# Cerebro.net
KiCad netlist of a schematic drawn in EasyEDA Pro
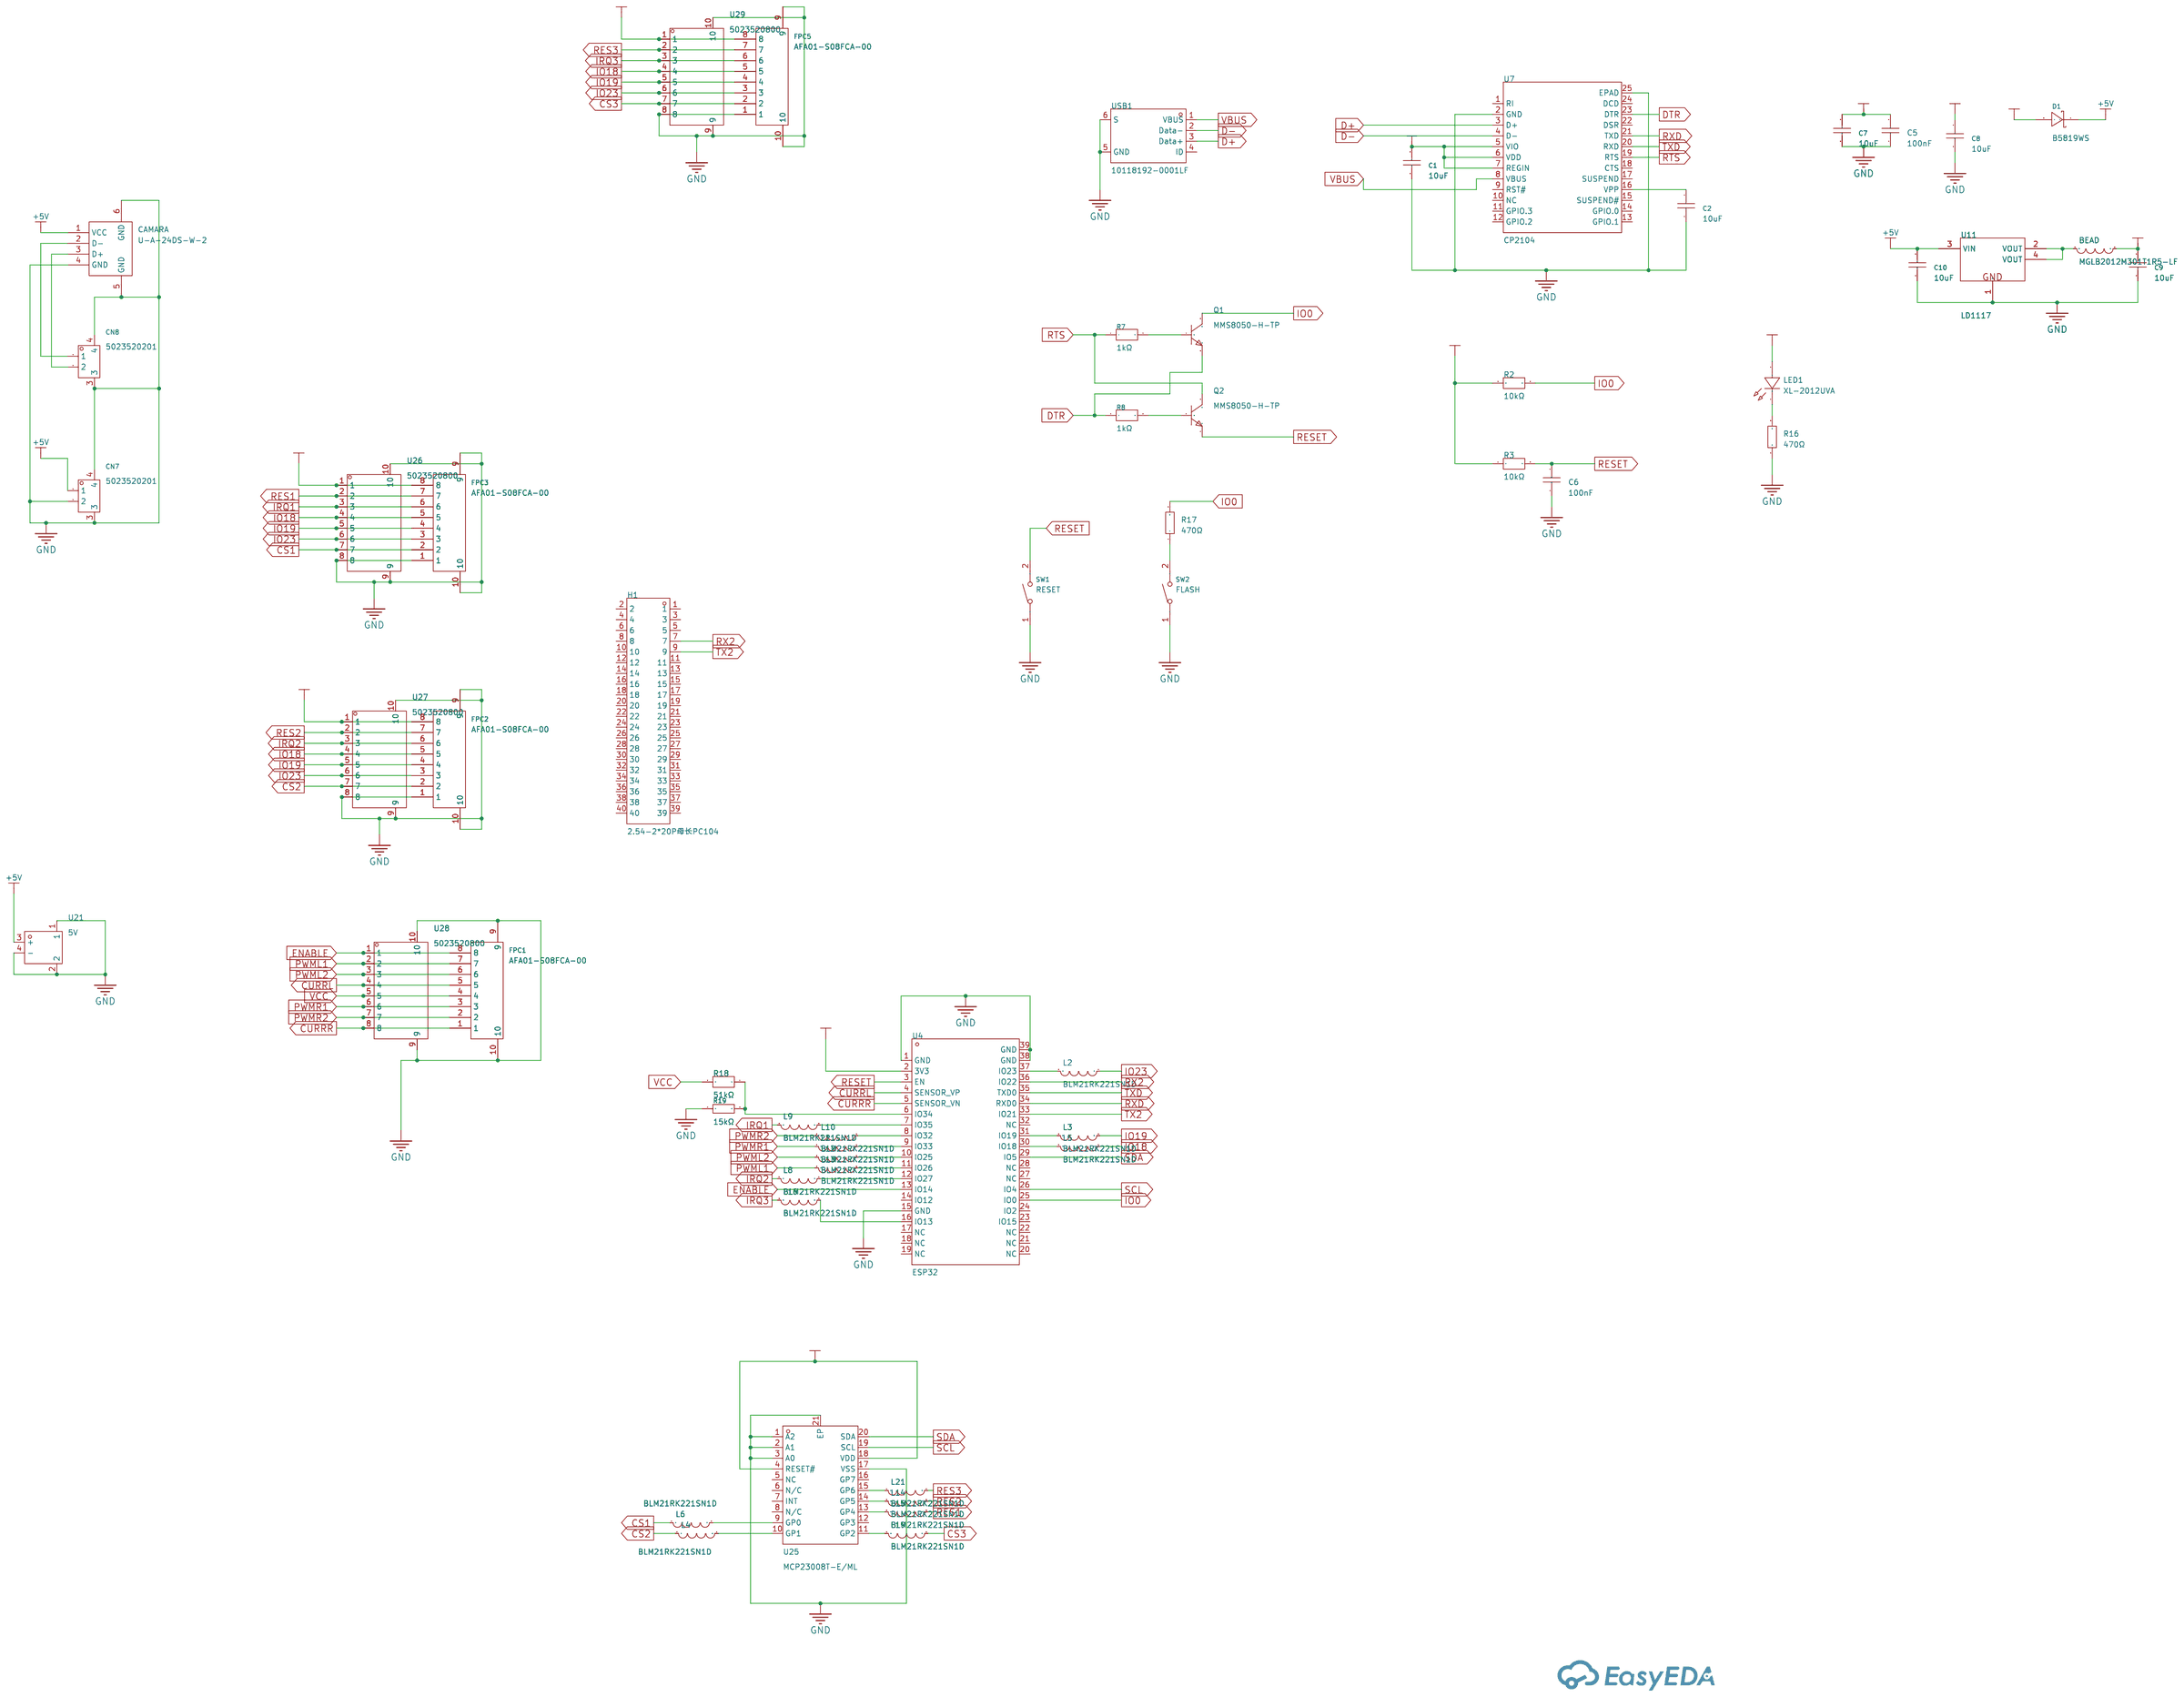
[diagram p0: schematic sheet]

(export (version "E")
  (design (tool "Eeschema 10.0.6"))
  (components
    (comp (ref "BEAD")
      (value "MGLB2012M301T1R5-LF")
      (footprint "easyedapro:L0805")
      (fields (field (name "Manufacturer") "microgate(麦捷科技)"))
      (libsource (lib "easyedapro") (part "MGLB2012M301T1R5-LF"))
    )
    (comp (ref "C1")
      (value "10uF")
      (footprint "easyedapro:C0805")
      (fields
        (field (name "Manufacturer Part") "CL21A106KPFNNNE")
        (field (name "Manufacturer") "SAMSUNG(三星)")
      )
      (libsource (lib "easyedapro") (part "CL21A106KPFNNNE"))
    )
    (comp (ref "C2")
      (value "10uF")
      (footprint "easyedapro:C0805")
      (fields
        (field (name "Manufacturer Part") "CL21A106KPFNNNE")
        (field (name "Manufacturer") "SAMSUNG(三星)")
      )
      (libsource (lib "easyedapro") (part "CL21A106KPFNNNE"))
    )
    (comp (ref "C5")
      (value "100nF")
      (footprint "easyedapro:C0805")
      (description "Capacitance:100nF Tolerance:±5% Tolerance:±5% Voltage Rating:50V Temperature Coefficient:X7R")
      (fields (field (name "Manufacturer Part") "0805B104J500NT") (field (name "Manufacturer") "FH(风华)"))
      (libsource (lib "easyedapro") (part "0805B104J500NT"))
    )
    (comp (ref "C6")
      (value "100nF")
      (footprint "easyedapro:C0805")
      (description "Capacitance:100nF Tolerance:±5% Tolerance:±5% Voltage Rating:50V Temperature Coefficient:X7R")
      (fields (field (name "Manufacturer Part") "0805B104J500NT") (field (name "Manufacturer") "FH(风华)"))
      (libsource (lib "easyedapro") (part "0805B104J500NT"))
    )
    (comp (ref "C7")
      (value "10uF")
      (footprint "easyedapro:C0805")
      (fields
        (field (name "Manufacturer Part") "CL21A106KPFNNNE")
        (field (name "Manufacturer") "SAMSUNG(三星)")
      )
      (libsource (lib "easyedapro") (part "CL21A106KPFNNNE"))
    )
    (comp (ref "C8")
      (value "10uF")
      (footprint "easyedapro:C0805")
      (fields
        (field (name "Manufacturer Part") "CL21A106KPFNNNE")
        (field (name "Manufacturer") "SAMSUNG(三星)")
      )
      (libsource (lib "easyedapro") (part "CL21A106KPFNNNE"))
    )
    (comp (ref "C9")
      (value "10uF")
      (footprint "easyedapro:C0805")
      (fields
        (field (name "Manufacturer Part") "CL21A106KPFNNNE")
        (field (name "Manufacturer") "SAMSUNG(三星)")
      )
      (libsource (lib "easyedapro") (part "CL21A106KPFNNNE"))
    )
    (comp (ref "C10")
      (value "10uF")
      (footprint "easyedapro:C0805")
      (fields
        (field (name "Manufacturer Part") "CL21A106KPFNNNE")
        (field (name "Manufacturer") "SAMSUNG(三星)")
      )
      (libsource (lib "easyedapro") (part "CL21A106KPFNNNE"))
    )
    (comp (ref "CAMARA")
      (value "U-A-24DS-W-2")
      (footprint "easyedapro:USB-A-SMD_U-A-24DS-Y-1")
      (fields (field (name "Manufacturer") "韩国韩荣"))
      (libsource (lib "easyedapro") (part "U-A-24DS-W-2"))
    )
    (comp (ref "CN7")
      (value "5023520201")
      (footprint "easyedapro:CONN-SMD_2P-P2.00_MOLEX_5023520201")
      (fields (field (name "Manufacturer") "MOLEX"))
      (libsource (lib "easyedapro") (part "5023520201"))
    )
    (comp (ref "CN8")
      (value "5023520201")
      (footprint "easyedapro:CONN-SMD_2P-P2.00_MOLEX_5023520201")
      (fields (field (name "Manufacturer") "MOLEX"))
      (libsource (lib "easyedapro") (part "5023520201"))
    )
    (comp (ref "D1")
      (value "B5819WS")
      (footprint "easyedapro:SOD-323_L1.8-W1.3-LS2.5-RD")
      (fields (field (name "Manufacturer Part") "B5819WS-TP") (field (name "Manufacturer") "MCC(美微科)"))
      (libsource (lib "easyedapro") (part "B5819WS-TP"))
    )
    (comp (ref "FPC1")
      (value "AFA01-S08FCA-00")
      (footprint "easyedapro:FPC-SMD_8P-P1.00_FGS-XJ-H2.0")
      (fields (field (name "Manufacturer") "JS(钜硕电子)"))
      (libsource (lib "easyedapro") (part "AFA01-S08FCA-00"))
    )
    (comp (ref "FPC2")
      (value "AFA01-S08FCA-00")
      (footprint "easyedapro:FPC-SMD_8P-P1.00_FGS-XJ-H2.0")
      (fields (field (name "Manufacturer") "JS(钜硕电子)"))
      (libsource (lib "easyedapro") (part "AFA01-S08FCA-00"))
    )
    (comp (ref "FPC3")
      (value "AFA01-S08FCA-00")
      (footprint "easyedapro:FPC-SMD_8P-P1.00_FGS-XJ-H2.0")
      (fields (field (name "Manufacturer") "JS(钜硕电子)"))
      (libsource (lib "easyedapro") (part "AFA01-S08FCA-00"))
    )
    (comp (ref "FPC5")
      (value "AFA01-S08FCA-00")
      (footprint "easyedapro:FPC-SMD_8P-P1.00_FGS-XJ-H2.0")
      (fields (field (name "Manufacturer") "JS(钜硕电子)"))
      (libsource (lib "easyedapro") (part "AFA01-S08FCA-00"))
    )
    (comp (ref "H1")
      (value "2.54-2*20P母长PC104")
      (footprint "easyedapro:HDR-TH_40P-P2.54-V-F-R2-C20-S2.54-2")
      (fields (field (name "Manufacturer") "BOOMELE(博穆精密)"))
      (libsource (lib "easyedapro") (part "2.54mm 2*20P"))
    )
    (comp (ref "L2")
      (value "BLM21RK221SN1D")
      (footprint "easyedapro:L0805")
      (fields (field (name "Manufacturer") "muRata(村田)"))
      (libsource (lib "easyedapro") (part "BLM21RK221SN1D"))
    )
    (comp (ref "L3")
      (value "BLM21RK221SN1D")
      (footprint "easyedapro:L0805")
      (fields (field (name "Manufacturer") "muRata(村田)"))
      (libsource (lib "easyedapro") (part "BLM21RK221SN1D"))
    )
    (comp (ref "L4")
      (value "BLM21RK221SN1D")
      (footprint "easyedapro:L0805")
      (fields (field (name "Manufacturer") "muRata(村田)"))
      (libsource (lib "easyedapro") (part "BLM21RK221SN1D"))
    )
    (comp (ref "L5")
      (value "BLM21RK221SN1D")
      (footprint "easyedapro:L0805")
      (fields (field (name "Manufacturer") "muRata(村田)"))
      (libsource (lib "easyedapro") (part "BLM21RK221SN1D"))
    )
    (comp (ref "L6")
      (value "BLM21RK221SN1D")
      (footprint "easyedapro:L0805")
      (fields (field (name "Manufacturer") "muRata(村田)"))
      (libsource (lib "easyedapro") (part "BLM21RK221SN1D"))
    )
    (comp (ref "L8")
      (value "BLM21RK221SN1D")
      (footprint "easyedapro:L0805")
      (fields (field (name "Manufacturer") "muRata(村田)"))
      (libsource (lib "easyedapro") (part "BLM21RK221SN1D"))
    )
    (comp (ref "L9")
      (value "BLM21RK221SN1D")
      (footprint "easyedapro:L0805")
      (fields (field (name "Manufacturer") "muRata(村田)"))
      (libsource (lib "easyedapro") (part "BLM21RK221SN1D"))
    )
    (comp (ref "L10")
      (value "BLM21RK221SN1D")
      (footprint "easyedapro:L0805")
      (fields (field (name "Manufacturer") "muRata(村田)"))
      (libsource (lib "easyedapro") (part "BLM21RK221SN1D"))
    )
    (comp (ref "L11")
      (value "BLM21RK221SN1D")
      (footprint "easyedapro:L0805")
      (fields (field (name "Manufacturer") "muRata(村田)"))
      (libsource (lib "easyedapro") (part "BLM21RK221SN1D"))
    )
    (comp (ref "L12")
      (value "BLM21RK221SN1D")
      (footprint "easyedapro:L0805")
      (fields (field (name "Manufacturer") "muRata(村田)"))
      (libsource (lib "easyedapro") (part "BLM21RK221SN1D"))
    )
    (comp (ref "L13")
      (value "BLM21RK221SN1D")
      (footprint "easyedapro:L0805")
      (fields (field (name "Manufacturer") "muRata(村田)"))
      (libsource (lib "easyedapro") (part "BLM21RK221SN1D"))
    )
    (comp (ref "L14")
      (value "BLM21RK221SN1D")
      (footprint "easyedapro:L0805")
      (fields (field (name "Manufacturer") "muRata(村田)"))
      (libsource (lib "easyedapro") (part "BLM21RK221SN1D"))
    )
    (comp (ref "L15")
      (value "BLM21RK221SN1D")
      (footprint "easyedapro:L0805")
      (fields (field (name "Manufacturer") "muRata(村田)"))
      (libsource (lib "easyedapro") (part "BLM21RK221SN1D"))
    )
    (comp (ref "L16")
      (value "BLM21RK221SN1D")
      (footprint "easyedapro:L0805")
      (fields (field (name "Manufacturer") "muRata(村田)"))
      (libsource (lib "easyedapro") (part "BLM21RK221SN1D"))
    )
    (comp (ref "L19")
      (value "BLM21RK221SN1D")
      (footprint "easyedapro:L0805")
      (fields (field (name "Manufacturer") "muRata(村田)"))
      (libsource (lib "easyedapro") (part "BLM21RK221SN1D"))
    )
    (comp (ref "L21")
      (value "BLM21RK221SN1D")
      (footprint "easyedapro:L0805")
      (fields (field (name "Manufacturer") "muRata(村田)"))
      (libsource (lib "easyedapro") (part "BLM21RK221SN1D"))
    )
    (comp (ref "LED1")
      (value "XL-2012UVA")
      (footprint "easyedapro:LED0805-RD")
      (fields (field (name "Manufacturer") "XINGLIGHT(成兴光)"))
      (libsource (lib "easyedapro") (part "XL-2012UVA"))
    )
    (comp (ref "Q1")
      (value "MMS8050-H-TP")
      (footprint "easyedapro:SOT-23-3_L2.9-W1.3-P1.90-LS2.4-BR")
      (fields (field (name "Manufacturer") "MCC(美微科)"))
      (libsource (lib "easyedapro") (part "MMS8050-H-TP"))
    )
    (comp (ref "Q2")
      (value "MMS8050-H-TP")
      (footprint "easyedapro:SOT-23-3_L2.9-W1.3-P1.90-LS2.4-BR")
      (fields (field (name "Manufacturer") "MCC(美微科)"))
      (libsource (lib "easyedapro") (part "MMS8050-H-TP"))
    )
    (comp (ref "R2")
      (value "10kΩ")
      (footprint "easyedapro:R0805")
      (fields (field (name "Manufacturer Part") "ERJP06F1002V") (field (name "Manufacturer") "PANASONIC(松下)"))
      (libsource (lib "easyedapro") (part "ERJP06F1002V"))
    )
    (comp (ref "R3")
      (value "10kΩ")
      (footprint "easyedapro:R0805")
      (fields (field (name "Manufacturer Part") "ERJP06F1002V") (field (name "Manufacturer") "PANASONIC(松下)"))
      (libsource (lib "easyedapro") (part "ERJP06F1002V"))
    )
    (comp (ref "R7")
      (value "1kΩ")
      (footprint "easyedapro:R0805")
      (fields (field (name "Manufacturer Part") "ERJP06F1001V") (field (name "Manufacturer") "PANASONIC(松下)"))
      (libsource (lib "easyedapro") (part "ERJP06F1001V"))
    )
    (comp (ref "R8")
      (value "1kΩ")
      (footprint "easyedapro:R0805")
      (fields (field (name "Manufacturer Part") "ERJP06F1001V") (field (name "Manufacturer") "PANASONIC(松下)"))
      (libsource (lib "easyedapro") (part "ERJP06F1001V"))
    )
    (comp (ref "R16")
      (value "470Ω")
      (footprint "easyedapro:R0805")
      (fields (field (name "Manufacturer Part") "RC0805FR-07470RL") (field (name "Manufacturer") "YAGEO(国巨)"))
      (libsource (lib "easyedapro") (part "RC0805FR-07470RL"))
    )
    (comp (ref "R17")
      (value "470Ω")
      (footprint "easyedapro:R0805")
      (fields (field (name "Manufacturer Part") "RC0805FR-07470RL") (field (name "Manufacturer") "YAGEO(国巨)"))
      (libsource (lib "easyedapro") (part "RC0805FR-07470RL"))
    )
    (comp (ref "R18")
      (value "51kΩ")
      (footprint "easyedapro:R0805")
      (fields (field (name "Manufacturer Part") "FRC0805F5102TS") (field (name "Manufacturer") "FOJAN(富捷)"))
      (libsource (lib "easyedapro") (part "FRC0805F5102TS"))
    )
    (comp (ref "R19")
      (value "15kΩ")
      (footprint "easyedapro:R0805")
      (fields
        (field (name "Manufacturer Part") "0805W8F1502T5E")
        (field (name "Manufacturer") "UNI-ROYAL(厚声)")
      )
      (libsource (lib "easyedapro") (part "0805W8F1502T5E"))
    )
    (comp (ref "SW1")
      (value "RESET")
      (footprint "easyedapro:SW-SMD_L3.9-W3.0-P4.45")
      (fields (field (name "Manufacturer Part") "TS-1088-AR02016") (field (name "Manufacturer") "XUNPU(讯普)"))
      (libsource (lib "easyedapro") (part "TS-1088-AR02016"))
    )
    (comp (ref "SW2")
      (value "FLASH")
      (footprint "easyedapro:SW-SMD_L3.9-W3.0-P4.45")
      (fields (field (name "Manufacturer Part") "TS-1088-AR02016") (field (name "Manufacturer") "XUNPU(讯普)"))
      (libsource (lib "easyedapro") (part "TS-1088-AR02016"))
    )
    (comp (ref "U4")
      (value "ESP32")
      (footprint "easyedapro:WIFI-SMD_ESP32-WROVER-IE8MB")
      (fields
        (field (name "Manufacturer Part") "ESP32-WROVER-E-N8R8")
        (field (name "Manufacturer") "ESPRESSIF(乐鑫)")
      )
      (libsource (lib "easyedapro") (part "ESP32-WROVER-E-N8R8"))
    )
    (comp (ref "U7")
      (value "CP2104")
      (footprint "easyedapro:QFN-24_L4.0-W4.0-P0.50-BL-EP2.7")
      (fields
        (field (name "Manufacturer Part") "CP2104-F03-GMR")
        (field (name "Manufacturer") "SKYWORKS/SILICON LABS(芯科)")
      )
      (libsource (lib "easyedapro") (part "CP2104-F03-GM"))
    )
    (comp (ref "U11")
      (value "LD1117")
      (footprint "easyedapro:SOT-223-4_L6.5-W3.5-P2.30-LS7.0-BR")
      (fields (field (name "Manufacturer Part") "LD1117S33CTR") (field (name "Manufacturer") "ST(意法半导体)"))
      (libsource (lib "easyedapro") (part "LD1117S33CTR"))
    )
    (comp (ref "U21")
      (value "5V")
      (footprint "easyedapro:TH_2P-XT60PW-F")
      (fields (field (name "Manufacturer Part") "XT60PW-F") (field (name "Manufacturer") "AMASS(艾迈斯)"))
      (libsource (lib "easyedapro") (part "XT60PW-F_C428722"))
    )
    (comp (ref "U25")
      (value "MCP23008T-E/ML")
      (footprint "easyedapro:UQFN-20_L4.0-W4.0-P0.50-BL-EP2.7")
      (fields (field (name "Manufacturer") "MICROCHIP(美国微芯)"))
      (libsource (lib "easyedapro") (part "MCP23008T-E/ML"))
    )
    (comp (ref "U26")
      (value "5023520800")
      (footprint "easyedapro:CONN-SMD_5023520800")
      (fields (field (name "Manufacturer") "MOLEX"))
      (libsource (lib "easyedapro") (part "5023520800"))
    )
    (comp (ref "U27")
      (value "5023520800")
      (footprint "easyedapro:CONN-SMD_5023520800")
      (fields (field (name "Manufacturer") "MOLEX"))
      (libsource (lib "easyedapro") (part "5023520800"))
    )
    (comp (ref "U28")
      (value "5023520800")
      (footprint "easyedapro:CONN-SMD_5023520800")
      (fields (field (name "Manufacturer") "MOLEX"))
      (libsource (lib "easyedapro") (part "5023520800"))
    )
    (comp (ref "U29")
      (value "5023520800")
      (footprint "easyedapro:CONN-SMD_5023520800")
      (fields (field (name "Manufacturer") "MOLEX"))
      (libsource (lib "easyedapro") (part "5023520800"))
    )
    (comp (ref "USB1")
      (value "10118192-0001LF")
      (footprint "easyedapro:MICRO-USB-SMD_10118192-0001LF_1")
      (fields (field (name "Manufacturer") "Amphenol"))
      (libsource (lib "easyedapro") (part "10118192-0001LF"))
    )
  )
  (nets
    (net (code "1") (name "+3V3") (class "Default")
      (node (ref "BEAD") (pin "1") (pinfunction "1_1") (pintype "unspecified"))
      (node (ref "C1") (pin "2") (pinfunction "2_2") (pintype "input"))
      (node (ref "C8") (pin "2") (pinfunction "2_2") (pintype "input"))
      (node (ref "C9") (pin "2") (pinfunction "2_2") (pintype "input"))
      (node (ref "FPC2") (pin "8") (pinfunction "8_8") (pintype "input"))
      (node (ref "FPC3") (pin "8") (pinfunction "8_8") (pintype "input"))
      (node (ref "FPC5") (pin "8") (pinfunction "8_8") (pintype "input"))
      (node (ref "LED1") (pin "2") (pinfunction "A_2") (pintype "unspecified"))
      (node (ref "R2") (pin "1") (pinfunction "1_1") (pintype "unspecified"))
      (node (ref "R3") (pin "1") (pinfunction "1_1") (pintype "unspecified"))
      (node (ref "U25") (pin "18") (pinfunction "VDD_18") (pintype "unspecified"))
      (node (ref "U25") (pin "4") (pinfunction "RESET#_4") (pintype "unspecified"))
      (node (ref "U26") (pin "1") (pinfunction "1_1") (pintype "unspecified"))
      (node (ref "U27") (pin "1") (pinfunction "1_1") (pintype "unspecified"))
      (node (ref "U29") (pin "1") (pinfunction "1_1") (pintype "unspecified"))
      (node (ref "U4") (pin "2") (pinfunction "3V3_2") (pintype "unspecified"))
      (node (ref "U7") (pin "5") (pinfunction "VIO_5") (pintype "unspecified"))
      (node (ref "U7") (pin "6") (pinfunction "VDD_6") (pintype "unspecified"))
      (node (ref "U7") (pin "7") (pinfunction "REGIN_7") (pintype "unspecified"))
    )
    (net (code "2") (name "+5V") (class "Default")
      (node (ref "C10") (pin "2") (pinfunction "2_2") (pintype "input"))
      (node (ref "CAMARA") (pin "1") (pinfunction "VCC_1") (pintype "unspecified"))
      (node (ref "CN7") (pin "1") (pinfunction "1_1") (pintype "input"))
      (node (ref "D1") (pin "1") (pinfunction "K_1") (pintype "input"))
      (node (ref "U11") (pin "3") (pinfunction "VIN_3") (pintype "unspecified"))
      (node (ref "U21") (pin "3") (pinfunction "+_3") (pintype "unspecified"))
    )
    (net (code "3") (name "CS1") (class "Default")
      (node (ref "FPC3") (pin "2") (pinfunction "2_2") (pintype "input"))
      (node (ref "L6") (pin "1") (pinfunction "1_1") (pintype "unspecified"))
      (node (ref "U26") (pin "7") (pinfunction "7_7") (pintype "unspecified"))
    )
    (net (code "4") (name "CS2") (class "Default")
      (node (ref "FPC2") (pin "2") (pinfunction "2_2") (pintype "input"))
      (node (ref "L4") (pin "1") (pinfunction "1_1") (pintype "unspecified"))
      (node (ref "U27") (pin "7") (pinfunction "7_7") (pintype "unspecified"))
    )
    (net (code "5") (name "CS3") (class "Default")
      (node (ref "FPC5") (pin "2") (pinfunction "2_2") (pintype "input"))
      (node (ref "L19") (pin "1") (pinfunction "1_1") (pintype "unspecified"))
      (node (ref "U29") (pin "7") (pinfunction "7_7") (pintype "unspecified"))
    )
    (net (code "6") (name "CURRL") (class "Default")
      (node (ref "FPC1") (pin "5") (pinfunction "5_5") (pintype "input"))
      (node (ref "U28") (pin "4") (pinfunction "4_4") (pintype "unspecified"))
      (node (ref "U4") (pin "4") (pinfunction "SENSOR_VP_4") (pintype "unspecified"))
    )
    (net (code "7") (name "CURRR") (class "Default")
      (node (ref "FPC1") (pin "1") (pinfunction "1_1") (pintype "input"))
      (node (ref "U28") (pin "8") (pinfunction "8_8") (pintype "unspecified"))
      (node (ref "U4") (pin "5") (pinfunction "SENSOR_VN_5") (pintype "unspecified"))
    )
    (net (code "8") (name "D+") (class "Default")
      (node (ref "U7") (pin "3") (pinfunction "D+_3") (pintype "unspecified"))
      (node (ref "USB1") (pin "3") (pinfunction "Data+_3") (pintype "unspecified"))
    )
    (net (code "9") (name "D-") (class "Default")
      (node (ref "U7") (pin "4") (pinfunction "D-_4") (pintype "unspecified"))
      (node (ref "USB1") (pin "2") (pinfunction "Data-_2") (pintype "unspecified"))
    )
    (net (code "10") (name "DTR") (class "Default")
      (node (ref "Q1") (pin "2") (pinfunction "E_2") (pintype "input"))
      (node (ref "R8") (pin "1") (pinfunction "1_1") (pintype "input"))
      (node (ref "U7") (pin "23") (pinfunction "DTR_23") (pintype "unspecified"))
    )
    (net (code "11") (name "ENABLE") (class "Default")
      (node (ref "FPC1") (pin "8") (pinfunction "8_8") (pintype "input"))
      (node (ref "U28") (pin "1") (pinfunction "1_1") (pintype "unspecified"))
      (node (ref "U4") (pin "13") (pinfunction "IO14_13") (pintype "unspecified"))
    )
    (net (code "12") (name "GND") (class "Default")
      (node (ref "C1") (pin "1") (pinfunction "1_1") (pintype "input"))
      (node (ref "C10") (pin "1") (pinfunction "1_1") (pintype "input"))
      (node (ref "C2") (pin "1") (pinfunction "1_1") (pintype "input"))
      (node (ref "C5") (pin "1") (pinfunction "1_1") (pintype "input"))
      (node (ref "C6") (pin "1") (pinfunction "1_1") (pintype "input"))
      (node (ref "C7") (pin "1") (pinfunction "1_1") (pintype "input"))
      (node (ref "C8") (pin "1") (pinfunction "1_1") (pintype "input"))
      (node (ref "C9") (pin "1") (pinfunction "1_1") (pintype "input"))
      (node (ref "CAMARA") (pin "4") (pinfunction "GND_4") (pintype "unspecified"))
      (node (ref "CAMARA") (pin "5") (pinfunction "GND_5") (pintype "unspecified"))
      (node (ref "CAMARA") (pin "6") (pinfunction "GND_6") (pintype "unspecified"))
      (node (ref "CN7") (pin "2") (pinfunction "2_2") (pintype "input"))
      (node (ref "CN7") (pin "3") (pinfunction "3_3") (pintype "input"))
      (node (ref "CN7") (pin "4") (pinfunction "4_4") (pintype "input"))
      (node (ref "CN8") (pin "3") (pinfunction "3_3") (pintype "input"))
      (node (ref "CN8") (pin "4") (pinfunction "4_4") (pintype "input"))
      (node (ref "FPC1") (pin "10") (pinfunction "10_10") (pintype "input"))
      (node (ref "FPC1") (pin "9") (pinfunction "9_9") (pintype "input"))
      (node (ref "FPC2") (pin "1") (pinfunction "1_1") (pintype "input"))
      (node (ref "FPC2") (pin "10") (pinfunction "10_10") (pintype "input"))
      (node (ref "FPC2") (pin "9") (pinfunction "9_9") (pintype "input"))
      (node (ref "FPC3") (pin "1") (pinfunction "1_1") (pintype "input"))
      (node (ref "FPC3") (pin "10") (pinfunction "10_10") (pintype "input"))
      (node (ref "FPC3") (pin "9") (pinfunction "9_9") (pintype "input"))
      (node (ref "FPC5") (pin "1") (pinfunction "1_1") (pintype "input"))
      (node (ref "FPC5") (pin "10") (pinfunction "10_10") (pintype "input"))
      (node (ref "FPC5") (pin "9") (pinfunction "9_9") (pintype "input"))
      (node (ref "R16") (pin "1") (pinfunction "1_1") (pintype "input"))
      (node (ref "R19") (pin "1") (pinfunction "1_1") (pintype "input"))
      (node (ref "SW1") (pin "1") (pinfunction "1_1") (pintype "input"))
      (node (ref "SW2") (pin "1") (pinfunction "1_1") (pintype "input"))
      (node (ref "U11") (pin "1") (pinfunction "GND_1") (pintype "unspecified"))
      (node (ref "U21") (pin "1") (pinfunction "1_1") (pintype "unspecified"))
      (node (ref "U21") (pin "2") (pinfunction "2_2") (pintype "unspecified"))
      (node (ref "U21") (pin "4") (pinfunction "-_4") (pintype "unspecified"))
      (node (ref "U25") (pin "1") (pinfunction "A2_1") (pintype "unspecified"))
      (node (ref "U25") (pin "17") (pinfunction "VSS_17") (pintype "unspecified"))
      (node (ref "U25") (pin "2") (pinfunction "A1_2") (pintype "unspecified"))
      (node (ref "U25") (pin "21") (pinfunction "EP_21") (pintype "unspecified"))
      (node (ref "U25") (pin "3") (pinfunction "A0_3") (pintype "unspecified"))
      (node (ref "U26") (pin "10") (pinfunction "10_10") (pintype "unspecified"))
      (node (ref "U26") (pin "8") (pinfunction "8_8") (pintype "unspecified"))
      (node (ref "U26") (pin "9") (pinfunction "9_9") (pintype "unspecified"))
      (node (ref "U27") (pin "10") (pinfunction "10_10") (pintype "unspecified"))
      (node (ref "U27") (pin "8") (pinfunction "8_8") (pintype "unspecified"))
      (node (ref "U27") (pin "9") (pinfunction "9_9") (pintype "unspecified"))
      (node (ref "U28") (pin "10") (pinfunction "10_10") (pintype "unspecified"))
      (node (ref "U28") (pin "9") (pinfunction "9_9") (pintype "unspecified"))
      (node (ref "U29") (pin "10") (pinfunction "10_10") (pintype "unspecified"))
      (node (ref "U29") (pin "8") (pinfunction "8_8") (pintype "unspecified"))
      (node (ref "U29") (pin "9") (pinfunction "9_9") (pintype "unspecified"))
      (node (ref "U4") (pin "1") (pinfunction "GND_1") (pintype "unspecified"))
      (node (ref "U4") (pin "15") (pinfunction "GND_15") (pintype "unspecified"))
      (node (ref "U4") (pin "38") (pinfunction "GND_38") (pintype "unspecified"))
      (node (ref "U4") (pin "39") (pinfunction "GND_39") (pintype "unspecified"))
      (node (ref "U7") (pin "2") (pinfunction "GND_2") (pintype "unspecified"))
      (node (ref "U7") (pin "25") (pinfunction "EPAD_25") (pintype "unspecified"))
      (node (ref "USB1") (pin "5") (pinfunction "GND_5") (pintype "unspecified"))
      (node (ref "USB1") (pin "6") (pinfunction "S_6") (pintype "unspecified"))
    )
    (net (code "13") (name "IO0") (class "Default")
      (node (ref "Q1") (pin "3") (pinfunction "C_3") (pintype "input"))
      (node (ref "R17") (pin "2") (pinfunction "2_2") (pintype "input"))
      (node (ref "R2") (pin "2") (pinfunction "2_2") (pintype "unspecified"))
      (node (ref "U4") (pin "25") (pinfunction "IO0_25") (pintype "unspecified"))
    )
    (net (code "14") (name "IO18") (class "Default")
      (node (ref "FPC2") (pin "5") (pinfunction "5_5") (pintype "input"))
      (node (ref "FPC3") (pin "5") (pinfunction "5_5") (pintype "input"))
      (node (ref "FPC5") (pin "5") (pinfunction "5_5") (pintype "input"))
      (node (ref "L5") (pin "1") (pinfunction "1_1") (pintype "unspecified"))
      (node (ref "U26") (pin "4") (pinfunction "4_4") (pintype "unspecified"))
      (node (ref "U27") (pin "4") (pinfunction "4_4") (pintype "unspecified"))
      (node (ref "U29") (pin "4") (pinfunction "4_4") (pintype "unspecified"))
    )
    (net (code "15") (name "IO19") (class "Default")
      (node (ref "FPC2") (pin "4") (pinfunction "4_4") (pintype "input"))
      (node (ref "FPC3") (pin "4") (pinfunction "4_4") (pintype "input"))
      (node (ref "FPC5") (pin "4") (pinfunction "4_4") (pintype "input"))
      (node (ref "L3") (pin "1") (pinfunction "1_1") (pintype "unspecified"))
      (node (ref "U26") (pin "5") (pinfunction "5_5") (pintype "unspecified"))
      (node (ref "U27") (pin "5") (pinfunction "5_5") (pintype "unspecified"))
      (node (ref "U29") (pin "5") (pinfunction "5_5") (pintype "unspecified"))
    )
    (net (code "16") (name "IO23") (class "Default")
      (node (ref "FPC2") (pin "3") (pinfunction "3_3") (pintype "input"))
      (node (ref "FPC3") (pin "3") (pinfunction "3_3") (pintype "input"))
      (node (ref "FPC5") (pin "3") (pinfunction "3_3") (pintype "input"))
      (node (ref "L2") (pin "1") (pinfunction "1_1") (pintype "unspecified"))
      (node (ref "U26") (pin "6") (pinfunction "6_6") (pintype "unspecified"))
      (node (ref "U27") (pin "6") (pinfunction "6_6") (pintype "unspecified"))
      (node (ref "U29") (pin "6") (pinfunction "6_6") (pintype "unspecified"))
    )
    (net (code "17") (name "IRQ1") (class "Default")
      (node (ref "FPC3") (pin "6") (pinfunction "6_6") (pintype "input"))
      (node (ref "L9") (pin "2") (pinfunction "2_2") (pintype "unspecified"))
      (node (ref "U26") (pin "3") (pinfunction "3_3") (pintype "unspecified"))
    )
    (net (code "18") (name "IRQ2") (class "Default")
      (node (ref "FPC2") (pin "6") (pinfunction "6_6") (pintype "input"))
      (node (ref "L8") (pin "2") (pinfunction "2_2") (pintype "unspecified"))
      (node (ref "U27") (pin "3") (pinfunction "3_3") (pintype "unspecified"))
    )
    (net (code "19") (name "IRQ3") (class "Default")
      (node (ref "FPC5") (pin "6") (pinfunction "6_6") (pintype "input"))
      (node (ref "L16") (pin "2") (pinfunction "2_2") (pintype "unspecified"))
      (node (ref "U29") (pin "3") (pinfunction "3_3") (pintype "unspecified"))
    )
    (net (code "20") (name "Net-(BEAD-Pad2)") (class "Default")
      (node (ref "BEAD") (pin "2") (pinfunction "2_2") (pintype "unspecified"))
      (node (ref "U11") (pin "2") (pinfunction "VOUT_2") (pintype "unspecified"))
      (node (ref "U11") (pin "4") (pinfunction "VOUT_4") (pintype "unspecified"))
    )
    (net (code "21") (name "Net-(CAMARA-D+)") (class "Default")
      (node (ref "CAMARA") (pin "3") (pinfunction "D+_3") (pintype "unspecified"))
      (node (ref "CN8") (pin "2") (pinfunction "2_2") (pintype "input"))
    )
    (net (code "22") (name "Net-(CAMARA-D-)") (class "Default")
      (node (ref "CAMARA") (pin "2") (pinfunction "D-_2") (pintype "unspecified"))
      (node (ref "CN8") (pin "1") (pinfunction "1_1") (pintype "input"))
    )
    (net (code "23") (name "Net-(LED1-K)") (class "Default")
      (node (ref "LED1") (pin "1") (pinfunction "K_1") (pintype "unspecified"))
      (node (ref "R16") (pin "2") (pinfunction "2_2") (pintype "input"))
    )
    (net (code "24") (name "Net-(Q1-B)") (class "Default")
      (node (ref "Q1") (pin "1") (pinfunction "B_1") (pintype "input"))
      (node (ref "R7") (pin "2") (pinfunction "2_2") (pintype "input"))
    )
    (net (code "25") (name "Net-(Q2-B)") (class "Default")
      (node (ref "Q2") (pin "1") (pinfunction "B_1") (pintype "input"))
      (node (ref "R8") (pin "2") (pinfunction "2_2") (pintype "input"))
    )
    (net (code "26") (name "Net-(R17-Pad1)") (class "Default")
      (node (ref "R17") (pin "1") (pinfunction "1_1") (pintype "input"))
      (node (ref "SW2") (pin "2") (pinfunction "2_2") (pintype "input"))
    )
    (net (code "27") (name "Net-(U4-IO13)") (class "Default")
      (node (ref "L16") (pin "1") (pinfunction "1_1") (pintype "unspecified"))
      (node (ref "U4") (pin "16") (pinfunction "IO13_16") (pintype "unspecified"))
    )
    (net (code "28") (name "Net-(U4-IO18)") (class "Default")
      (node (ref "L5") (pin "2") (pinfunction "2_2") (pintype "unspecified"))
      (node (ref "U4") (pin "30") (pinfunction "IO18_30") (pintype "unspecified"))
    )
    (net (code "29") (name "Net-(U4-IO19)") (class "Default")
      (node (ref "L3") (pin "2") (pinfunction "2_2") (pintype "unspecified"))
      (node (ref "U4") (pin "31") (pinfunction "IO19_31") (pintype "unspecified"))
    )
    (net (code "30") (name "Net-(U4-IO23)") (class "Default")
      (node (ref "L2") (pin "2") (pinfunction "2_2") (pintype "unspecified"))
      (node (ref "U4") (pin "37") (pinfunction "IO23_37") (pintype "unspecified"))
    )
    (net (code "31") (name "Net-(U4-IO25)") (class "Default")
      (node (ref "L12") (pin "1") (pinfunction "1_1") (pintype "unspecified"))
      (node (ref "U4") (pin "10") (pinfunction "IO25_10") (pintype "unspecified"))
    )
    (net (code "32") (name "Net-(U4-IO26)") (class "Default")
      (node (ref "L13") (pin "1") (pinfunction "1_1") (pintype "unspecified"))
      (node (ref "U4") (pin "11") (pinfunction "IO26_11") (pintype "unspecified"))
    )
    (net (code "33") (name "Net-(U4-IO27)") (class "Default")
      (node (ref "L8") (pin "1") (pinfunction "1_1") (pintype "unspecified"))
      (node (ref "U4") (pin "12") (pinfunction "IO27_12") (pintype "unspecified"))
    )
    (net (code "34") (name "Net-(U4-IO32)") (class "Default")
      (node (ref "L10") (pin "1") (pinfunction "1_1") (pintype "unspecified"))
      (node (ref "U4") (pin "8") (pinfunction "IO32_8") (pintype "unspecified"))
    )
    (net (code "35") (name "Net-(U4-IO33)") (class "Default")
      (node (ref "L11") (pin "1") (pinfunction "1_1") (pintype "unspecified"))
      (node (ref "U4") (pin "9") (pinfunction "IO33_9") (pintype "unspecified"))
    )
    (net (code "36") (name "Net-(U4-IO34)") (class "Default")
      (node (ref "R18") (pin "1") (pinfunction "1_1") (pintype "unspecified"))
      (node (ref "R19") (pin "2") (pinfunction "2_2") (pintype "input"))
      (node (ref "U4") (pin "6") (pinfunction "IO34_6") (pintype "unspecified"))
    )
    (net (code "37") (name "Net-(U4-IO35)") (class "Default")
      (node (ref "L9") (pin "1") (pinfunction "1_1") (pintype "unspecified"))
      (node (ref "U4") (pin "7") (pinfunction "IO35_7") (pintype "unspecified"))
    )
    (net (code "38") (name "Net-(U7-VPP)") (class "Default")
      (node (ref "C2") (pin "2") (pinfunction "2_2") (pintype "input"))
      (node (ref "U7") (pin "16") (pinfunction "VPP_16") (pintype "unspecified"))
    )
    (net (code "39") (name "Net-(U25-GP0)") (class "Default")
      (node (ref "L6") (pin "2") (pinfunction "2_2") (pintype "unspecified"))
      (node (ref "U25") (pin "9") (pinfunction "GP0_9") (pintype "unspecified"))
    )
    (net (code "40") (name "Net-(U25-GP1)") (class "Default")
      (node (ref "L4") (pin "2") (pinfunction "2_2") (pintype "unspecified"))
      (node (ref "U25") (pin "10") (pinfunction "GP1_10") (pintype "unspecified"))
    )
    (net (code "41") (name "Net-(U25-GP2)") (class "Default")
      (node (ref "L19") (pin "2") (pinfunction "2_2") (pintype "unspecified"))
      (node (ref "U25") (pin "11") (pinfunction "GP2_11") (pintype "unspecified"))
    )
    (net (code "42") (name "Net-(U25-GP4)") (class "Default")
      (node (ref "L15") (pin "1") (pinfunction "1_1") (pintype "unspecified"))
      (node (ref "U25") (pin "13") (pinfunction "GP4_13") (pintype "unspecified"))
    )
    (net (code "43") (name "Net-(U25-GP5)") (class "Default")
      (node (ref "L14") (pin "1") (pinfunction "1_1") (pintype "unspecified"))
      (node (ref "U25") (pin "14") (pinfunction "GP5_14") (pintype "unspecified"))
    )
    (net (code "44") (name "Net-(U25-GP6)") (class "Default")
      (node (ref "L21") (pin "1") (pinfunction "1_1") (pintype "unspecified"))
      (node (ref "U25") (pin "15") (pinfunction "GP6_15") (pintype "unspecified"))
    )
    (net (code "45") (name "PWML1") (class "Default")
      (node (ref "FPC1") (pin "7") (pinfunction "7_7") (pintype "input"))
      (node (ref "L13") (pin "2") (pinfunction "2_2") (pintype "unspecified"))
      (node (ref "U28") (pin "2") (pinfunction "2_2") (pintype "unspecified"))
    )
    (net (code "46") (name "PWML2") (class "Default")
      (node (ref "FPC1") (pin "6") (pinfunction "6_6") (pintype "input"))
      (node (ref "L12") (pin "2") (pinfunction "2_2") (pintype "unspecified"))
      (node (ref "U28") (pin "3") (pinfunction "3_3") (pintype "unspecified"))
    )
    (net (code "47") (name "PWMR1") (class "Default")
      (node (ref "FPC1") (pin "3") (pinfunction "3_3") (pintype "input"))
      (node (ref "L11") (pin "2") (pinfunction "2_2") (pintype "unspecified"))
      (node (ref "U28") (pin "6") (pinfunction "6_6") (pintype "unspecified"))
    )
    (net (code "48") (name "PWMR2") (class "Default")
      (node (ref "FPC1") (pin "2") (pinfunction "2_2") (pintype "input"))
      (node (ref "L10") (pin "2") (pinfunction "2_2") (pintype "unspecified"))
      (node (ref "U28") (pin "7") (pinfunction "7_7") (pintype "unspecified"))
    )
    (net (code "49") (name "RES1") (class "Default")
      (node (ref "FPC3") (pin "7") (pinfunction "7_7") (pintype "input"))
      (node (ref "L15") (pin "2") (pinfunction "2_2") (pintype "unspecified"))
      (node (ref "U26") (pin "2") (pinfunction "2_2") (pintype "unspecified"))
    )
    (net (code "50") (name "RES2") (class "Default")
      (node (ref "FPC2") (pin "7") (pinfunction "7_7") (pintype "input"))
      (node (ref "L14") (pin "2") (pinfunction "2_2") (pintype "unspecified"))
      (node (ref "U27") (pin "2") (pinfunction "2_2") (pintype "unspecified"))
    )
    (net (code "51") (name "RES3") (class "Default")
      (node (ref "FPC5") (pin "7") (pinfunction "7_7") (pintype "input"))
      (node (ref "L21") (pin "2") (pinfunction "2_2") (pintype "unspecified"))
      (node (ref "U29") (pin "2") (pinfunction "2_2") (pintype "unspecified"))
    )
    (net (code "52") (name "RESET") (class "Default")
      (node (ref "C6") (pin "2") (pinfunction "2_2") (pintype "input"))
      (node (ref "Q2") (pin "2") (pinfunction "E_2") (pintype "input"))
      (node (ref "R3") (pin "2") (pinfunction "2_2") (pintype "unspecified"))
      (node (ref "SW1") (pin "2") (pinfunction "2_2") (pintype "input"))
      (node (ref "U4") (pin "3") (pinfunction "EN_3") (pintype "unspecified"))
    )
    (net (code "53") (name "RTS") (class "Default")
      (node (ref "Q2") (pin "3") (pinfunction "C_3") (pintype "input"))
      (node (ref "R7") (pin "1") (pinfunction "1_1") (pintype "input"))
      (node (ref "U7") (pin "19") (pinfunction "RTS_19") (pintype "unspecified"))
    )
    (net (code "54") (name "RX2") (class "Default")
      (node (ref "H1") (pin "7") (pinfunction "7_7") (pintype "unspecified"))
      (node (ref "U4") (pin "36") (pinfunction "IO22_36") (pintype "unspecified"))
    )
    (net (code "55") (name "RXD") (class "Default")
      (node (ref "U4") (pin "34") (pinfunction "RXD0_34") (pintype "unspecified"))
      (node (ref "U7") (pin "21") (pinfunction "TXD_21") (pintype "unspecified"))
    )
    (net (code "56") (name "SCL") (class "Default")
      (node (ref "U25") (pin "19") (pinfunction "SCL_19") (pintype "unspecified"))
      (node (ref "U4") (pin "26") (pinfunction "IO4_26") (pintype "unspecified"))
    )
    (net (code "57") (name "SDA") (class "Default")
      (node (ref "U25") (pin "20") (pinfunction "SDA_20") (pintype "unspecified"))
      (node (ref "U4") (pin "29") (pinfunction "IO5_29") (pintype "unspecified"))
    )
    (net (code "58") (name "TX2") (class "Default")
      (node (ref "H1") (pin "9") (pinfunction "9_9") (pintype "unspecified"))
      (node (ref "U4") (pin "33") (pinfunction "IO21_33") (pintype "unspecified"))
    )
    (net (code "59") (name "TXD") (class "Default")
      (node (ref "U4") (pin "35") (pinfunction "TXD0_35") (pintype "unspecified"))
      (node (ref "U7") (pin "20") (pinfunction "RXD_20") (pintype "unspecified"))
    )
    (net (code "60") (name "VBUS") (class "Default")
      (node (ref "C5") (pin "2") (pinfunction "2_2") (pintype "input"))
      (node (ref "C7") (pin "2") (pinfunction "2_2") (pintype "input"))
      (node (ref "D1") (pin "2") (pinfunction "A_2") (pintype "input"))
      (node (ref "U7") (pin "8") (pinfunction "VBUS_8") (pintype "unspecified"))
      (node (ref "USB1") (pin "1") (pinfunction "VBUS_1") (pintype "unspecified"))
    )
    (net (code "61") (name "VCC") (class "Default")
      (node (ref "FPC1") (pin "4") (pinfunction "4_4") (pintype "input"))
      (node (ref "R18") (pin "2") (pinfunction "2_2") (pintype "unspecified"))
      (node (ref "U28") (pin "5") (pinfunction "5_5") (pintype "unspecified"))
    )
    (net (code "62") (name "unconnected-(H1-Pad1)") (class "Default")
      (node (ref "H1") (pin "1") (pinfunction "1_1") (pintype "unspecified"))
    )
    (net (code "63") (name "unconnected-(H1-Pad2)") (class "Default")
      (node (ref "H1") (pin "2") (pinfunction "2_2") (pintype "unspecified"))
    )
    (net (code "64") (name "unconnected-(H1-Pad3)") (class "Default")
      (node (ref "H1") (pin "3") (pinfunction "3_3") (pintype "unspecified"))
    )
    (net (code "65") (name "unconnected-(H1-Pad4)") (class "Default")
      (node (ref "H1") (pin "4") (pinfunction "4_4") (pintype "unspecified"))
    )
    (net (code "66") (name "unconnected-(H1-Pad5)") (class "Default")
      (node (ref "H1") (pin "5") (pinfunction "5_5") (pintype "unspecified"))
    )
    (net (code "67") (name "unconnected-(H1-Pad6)") (class "Default")
      (node (ref "H1") (pin "6") (pinfunction "6_6") (pintype "unspecified"))
    )
    (net (code "68") (name "unconnected-(H1-Pad8)") (class "Default")
      (node (ref "H1") (pin "8") (pinfunction "8_8") (pintype "unspecified"))
    )
    (net (code "69") (name "unconnected-(H1-Pad10)") (class "Default")
      (node (ref "H1") (pin "10") (pinfunction "10_10") (pintype "unspecified"))
    )
    (net (code "70") (name "unconnected-(H1-Pad11)") (class "Default")
      (node (ref "H1") (pin "11") (pinfunction "11_11") (pintype "unspecified"))
    )
    (net (code "71") (name "unconnected-(H1-Pad12)") (class "Default")
      (node (ref "H1") (pin "12") (pinfunction "12_12") (pintype "unspecified"))
    )
    (net (code "72") (name "unconnected-(H1-Pad13)") (class "Default")
      (node (ref "H1") (pin "13") (pinfunction "13_13") (pintype "unspecified"))
    )
    (net (code "73") (name "unconnected-(H1-Pad14)") (class "Default")
      (node (ref "H1") (pin "14") (pinfunction "14_14") (pintype "unspecified"))
    )
    (net (code "74") (name "unconnected-(H1-Pad15)") (class "Default")
      (node (ref "H1") (pin "15") (pinfunction "15_15") (pintype "unspecified"))
    )
    (net (code "75") (name "unconnected-(H1-Pad16)") (class "Default")
      (node (ref "H1") (pin "16") (pinfunction "16_16") (pintype "unspecified"))
    )
    (net (code "76") (name "unconnected-(H1-Pad17)") (class "Default")
      (node (ref "H1") (pin "17") (pinfunction "17_17") (pintype "unspecified"))
    )
    (net (code "77") (name "unconnected-(H1-Pad18)") (class "Default")
      (node (ref "H1") (pin "18") (pinfunction "18_18") (pintype "unspecified"))
    )
    (net (code "78") (name "unconnected-(H1-Pad19)") (class "Default")
      (node (ref "H1") (pin "19") (pinfunction "19_19") (pintype "unspecified"))
    )
    (net (code "79") (name "unconnected-(H1-Pad20)") (class "Default")
      (node (ref "H1") (pin "20") (pinfunction "20_20") (pintype "unspecified"))
    )
    (net (code "80") (name "unconnected-(H1-Pad21)") (class "Default")
      (node (ref "H1") (pin "21") (pinfunction "21_21") (pintype "unspecified"))
    )
    (net (code "81") (name "unconnected-(H1-Pad22)") (class "Default")
      (node (ref "H1") (pin "22") (pinfunction "22_22") (pintype "unspecified"))
    )
    (net (code "82") (name "unconnected-(H1-Pad23)") (class "Default")
      (node (ref "H1") (pin "23") (pinfunction "23_23") (pintype "unspecified"))
    )
    (net (code "83") (name "unconnected-(H1-Pad24)") (class "Default")
      (node (ref "H1") (pin "24") (pinfunction "24_24") (pintype "unspecified"))
    )
    (net (code "84") (name "unconnected-(H1-Pad25)") (class "Default")
      (node (ref "H1") (pin "25") (pinfunction "25_25") (pintype "unspecified"))
    )
    (net (code "85") (name "unconnected-(H1-Pad26)") (class "Default")
      (node (ref "H1") (pin "26") (pinfunction "26_26") (pintype "unspecified"))
    )
    (net (code "86") (name "unconnected-(H1-Pad27)") (class "Default")
      (node (ref "H1") (pin "27") (pinfunction "27_27") (pintype "unspecified"))
    )
    (net (code "87") (name "unconnected-(H1-Pad28)") (class "Default")
      (node (ref "H1") (pin "28") (pinfunction "28_28") (pintype "unspecified"))
    )
    (net (code "88") (name "unconnected-(H1-Pad29)") (class "Default")
      (node (ref "H1") (pin "29") (pinfunction "29_29") (pintype "unspecified"))
    )
    (net (code "89") (name "unconnected-(H1-Pad30)") (class "Default")
      (node (ref "H1") (pin "30") (pinfunction "30_30") (pintype "unspecified"))
    )
    (net (code "90") (name "unconnected-(H1-Pad31)") (class "Default")
      (node (ref "H1") (pin "31") (pinfunction "31_31") (pintype "unspecified"))
    )
    (net (code "91") (name "unconnected-(H1-Pad32)") (class "Default")
      (node (ref "H1") (pin "32") (pinfunction "32_32") (pintype "unspecified"))
    )
    (net (code "92") (name "unconnected-(H1-Pad33)") (class "Default")
      (node (ref "H1") (pin "33") (pinfunction "33_33") (pintype "unspecified"))
    )
    (net (code "93") (name "unconnected-(H1-Pad34)") (class "Default")
      (node (ref "H1") (pin "34") (pinfunction "34_34") (pintype "unspecified"))
    )
    (net (code "94") (name "unconnected-(H1-Pad35)") (class "Default")
      (node (ref "H1") (pin "35") (pinfunction "35_35") (pintype "unspecified"))
    )
    (net (code "95") (name "unconnected-(H1-Pad36)") (class "Default")
      (node (ref "H1") (pin "36") (pinfunction "36_36") (pintype "unspecified"))
    )
    (net (code "96") (name "unconnected-(H1-Pad37)") (class "Default")
      (node (ref "H1") (pin "37") (pinfunction "37_37") (pintype "unspecified"))
    )
    (net (code "97") (name "unconnected-(H1-Pad38)") (class "Default")
      (node (ref "H1") (pin "38") (pinfunction "38_38") (pintype "unspecified"))
    )
    (net (code "98") (name "unconnected-(H1-Pad39)") (class "Default")
      (node (ref "H1") (pin "39") (pinfunction "39_39") (pintype "unspecified"))
    )
    (net (code "99") (name "unconnected-(H1-Pad40)") (class "Default")
      (node (ref "H1") (pin "40") (pinfunction "40_40") (pintype "unspecified"))
    )
    (net (code "100") (name "unconnected-(U4-IO2-Pad24)") (class "Default")
      (node (ref "U4") (pin "24") (pinfunction "IO2_24") (pintype "unspecified"))
    )
    (net (code "101") (name "unconnected-(U4-IO12-Pad14)") (class "Default")
      (node (ref "U4") (pin "14") (pinfunction "IO12_14") (pintype "unspecified"))
    )
    (net (code "102") (name "unconnected-(U4-IO15-Pad23)") (class "Default")
      (node (ref "U4") (pin "23") (pinfunction "IO15_23") (pintype "unspecified"))
    )
    (net (code "103") (name "unconnected-(U4-NC-Pad17)") (class "Default")
      (node (ref "U4") (pin "17") (pinfunction "NC_17") (pintype "unspecified"))
    )
    (net (code "104") (name "unconnected-(U4-NC-Pad18)") (class "Default")
      (node (ref "U4") (pin "18") (pinfunction "NC_18") (pintype "unspecified"))
    )
    (net (code "105") (name "unconnected-(U4-NC-Pad19)") (class "Default")
      (node (ref "U4") (pin "19") (pinfunction "NC_19") (pintype "unspecified"))
    )
    (net (code "106") (name "unconnected-(U4-NC-Pad20)") (class "Default")
      (node (ref "U4") (pin "20") (pinfunction "NC_20") (pintype "unspecified"))
    )
    (net (code "107") (name "unconnected-(U4-NC-Pad21)") (class "Default")
      (node (ref "U4") (pin "21") (pinfunction "NC_21") (pintype "unspecified"))
    )
    (net (code "108") (name "unconnected-(U4-NC-Pad22)") (class "Default")
      (node (ref "U4") (pin "22") (pinfunction "NC_22") (pintype "unspecified"))
    )
    (net (code "109") (name "unconnected-(U4-NC-Pad27)") (class "Default")
      (node (ref "U4") (pin "27") (pinfunction "NC_27") (pintype "unspecified"))
    )
    (net (code "110") (name "unconnected-(U4-NC-Pad28)") (class "Default")
      (node (ref "U4") (pin "28") (pinfunction "NC_28") (pintype "unspecified"))
    )
    (net (code "111") (name "unconnected-(U4-NC-Pad32)") (class "Default")
      (node (ref "U4") (pin "32") (pinfunction "NC_32") (pintype "unspecified"))
    )
    (net (code "112") (name "unconnected-(U7-CTS-Pad18)") (class "Default")
      (node (ref "U7") (pin "18") (pinfunction "CTS_18") (pintype "unspecified"))
    )
    (net (code "113") (name "unconnected-(U7-DCD-Pad24)") (class "Default")
      (node (ref "U7") (pin "24") (pinfunction "DCD_24") (pintype "unspecified"))
    )
    (net (code "114") (name "unconnected-(U7-DSR-Pad22)") (class "Default")
      (node (ref "U7") (pin "22") (pinfunction "DSR_22") (pintype "unspecified"))
    )
    (net (code "115") (name "unconnected-(U7-GPIO.0-Pad14)") (class "Default")
      (node (ref "U7") (pin "14") (pinfunction "GPIO.0_14") (pintype "unspecified"))
    )
    (net (code "116") (name "unconnected-(U7-GPIO.1-Pad13)") (class "Default")
      (node (ref "U7") (pin "13") (pinfunction "GPIO.1_13") (pintype "unspecified"))
    )
    (net (code "117") (name "unconnected-(U7-GPIO.2-Pad12)") (class "Default")
      (node (ref "U7") (pin "12") (pinfunction "GPIO.2_12") (pintype "unspecified"))
    )
    (net (code "118") (name "unconnected-(U7-GPIO.3-Pad11)") (class "Default")
      (node (ref "U7") (pin "11") (pinfunction "GPIO.3_11") (pintype "unspecified"))
    )
    (net (code "119") (name "unconnected-(U7-NC-Pad10)") (class "Default")
      (node (ref "U7") (pin "10") (pinfunction "NC_10") (pintype "unspecified"))
    )
    (net (code "120") (name "unconnected-(U7-RI-Pad1)") (class "Default")
      (node (ref "U7") (pin "1") (pinfunction "RI_1") (pintype "unspecified"))
    )
    (net (code "121") (name "unconnected-(U7-RST#-Pad9)") (class "Default")
      (node (ref "U7") (pin "9") (pinfunction "RST#_9") (pintype "unspecified"))
    )
    (net (code "122") (name "unconnected-(U7-SUSPEND#-Pad15)") (class "Default")
      (node (ref "U7") (pin "15") (pinfunction "SUSPEND#_15") (pintype "unspecified"))
    )
    (net (code "123") (name "unconnected-(U7-SUSPEND-Pad17)") (class "Default")
      (node (ref "U7") (pin "17") (pinfunction "SUSPEND_17") (pintype "unspecified"))
    )
    (net (code "124") (name "unconnected-(U25-GP3-Pad12)") (class "Default")
      (node (ref "U25") (pin "12") (pinfunction "GP3_12") (pintype "unspecified"))
    )
    (net (code "125") (name "unconnected-(U25-GP7-Pad16)") (class "Default")
      (node (ref "U25") (pin "16") (pinfunction "GP7_16") (pintype "unspecified"))
    )
    (net (code "126") (name "unconnected-(U25-INT-Pad7)") (class "Default")
      (node (ref "U25") (pin "7") (pinfunction "INT_7") (pintype "unspecified"))
    )
    (net (code "127") (name "unconnected-(U25-NC-Pad5)") (class "Default")
      (node (ref "U25") (pin "5") (pinfunction "NC_5") (pintype "unspecified"))
    )
    (net (code "128") (name "unconnected-(U25-N{slash}C-Pad6)") (class "Default")
      (node (ref "U25") (pin "6") (pinfunction "N/C_6") (pintype "unspecified"))
    )
    (net (code "129") (name "unconnected-(U25-N{slash}C-Pad8)") (class "Default")
      (node (ref "U25") (pin "8") (pinfunction "N/C_8") (pintype "unspecified"))
    )
    (net (code "130") (name "unconnected-(USB1-ID-Pad4)") (class "Default")
      (node (ref "USB1") (pin "4") (pinfunction "ID_4") (pintype "unspecified"))
    )
  )
)
